# GSM-Board.net
KiCad netlist of a schematic drawn in Altium Designer
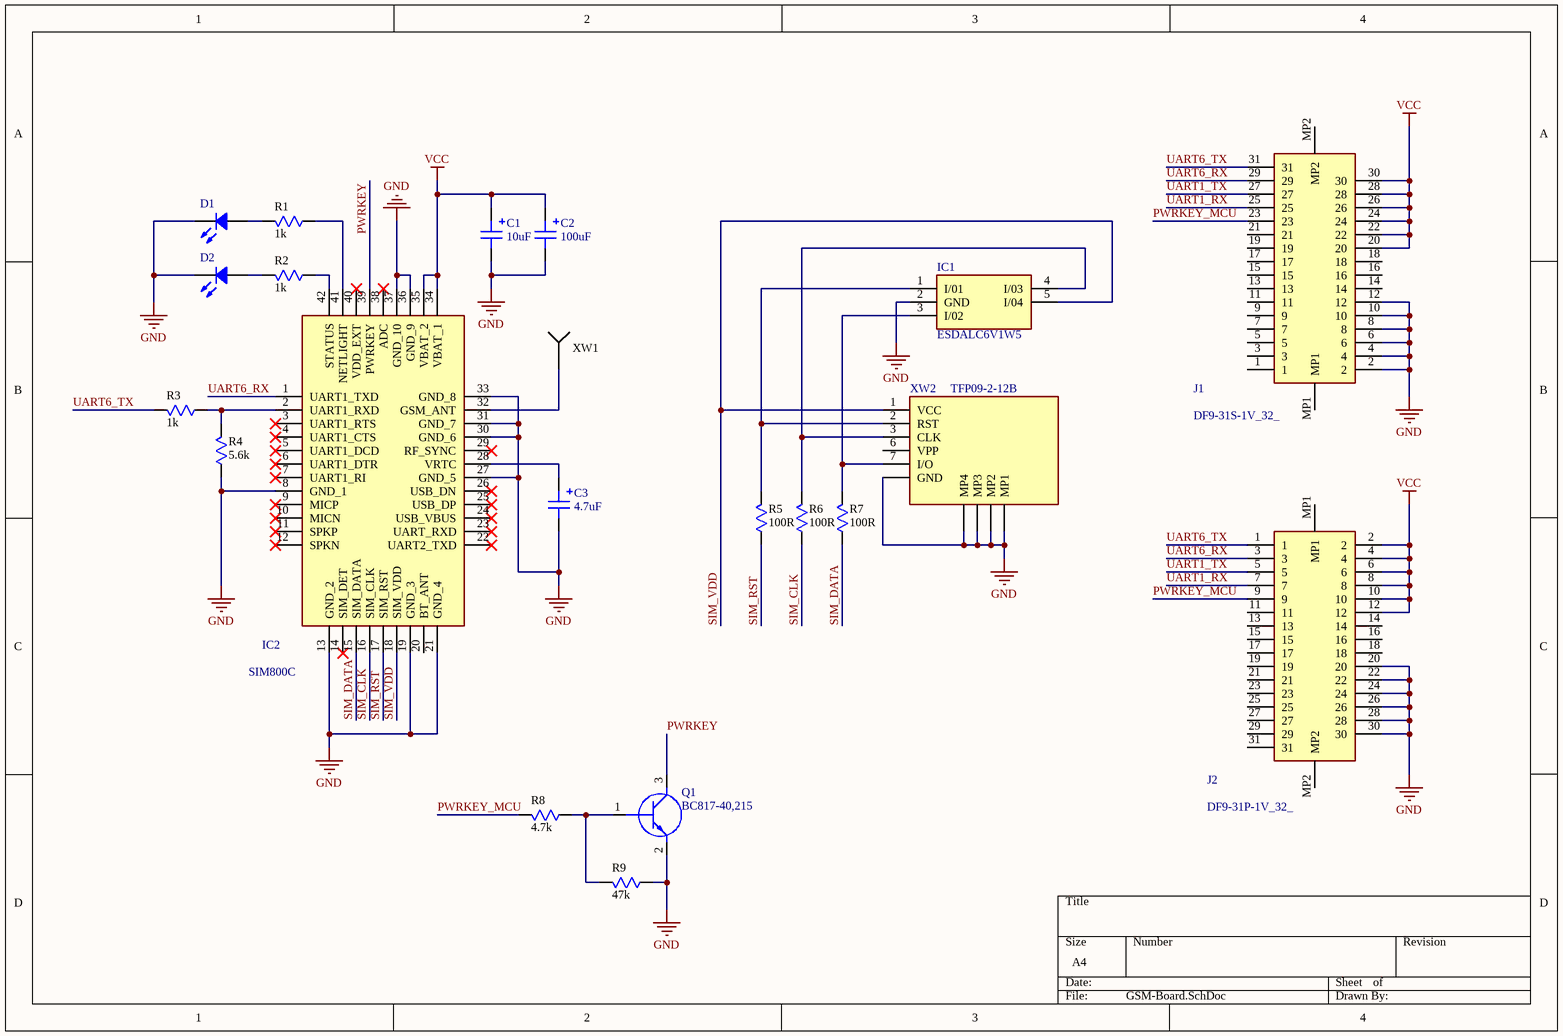
[diagram p0: GSM-Board.SchDoc]

(export (version "E")
  (design (tool "Eeschema 10.0.6"))
  (components
    (comp (ref "C1")
      (value "10uF")
      (footprint "PcbLib:CAP: TANTAL-B")
      (description "SMD Capacitor Polar")
      (libsource (lib "Schlib") (part "Capacitor_polar"))
    )
    (comp (ref "C2")
      (value "100uF")
      (footprint "PcbLib:CAP: TANTAL-D")
      (description "SMD Capacitor Polar")
      (libsource (lib "Schlib") (part "Capacitor_polar"))
    )
    (comp (ref "C3")
      (value "4.7uF")
      (footprint "PcbLib:CAP: TANTAL-A")
      (description "SMD Capacitor Polar")
      (libsource (lib "Schlib") (part "Capacitor_polar"))
    )
    (comp (ref "D1")
      (value "~")
      (footprint "PcbLib:LED0805")
      (description "Chip LED")
      (libsource (lib "Schlib") (part "LED"))
    )
    (comp (ref "D2")
      (value "~")
      (footprint "PcbLib:LED0805")
      (description "Chip LED")
      (libsource (lib "Schlib") (part "LED"))
    )
    (comp (ref "IC1")
      (value "ESDALC6V1W5")
      (footprint "PcbLib:SOT65P210X110-5N")
      (description "Integrated Circuit")
      (fields (field (name "MOUSER PART NUMBER") "511-ESDALC6V1W5"))
      (libsource (lib "*") (part "ESDALC6V1W5"))
    )
    (comp (ref "IC2")
      (value "SIM800C")
      (footprint "PcbLib:SIM800C")
      (description "Integrated Circuit")
      (fields (field (name "MANUFACTURER_PART_NUMBER") "-SIM800C"))
      (libsource (lib "Schlib") (part "-SIM800C"))
    )
    (comp (ref "J1")
      (value "DF9-31S-1V_32_")
      (footprint "PcbLib:DF931S1V32")
      (description "Connector")
      (fields
        (field (name "MANUFACTURER_PART_NUMBER") "DF9-31S-1V(32)")
        (field (name "MOUSER PART NUMBER") "798-DF9-31S-1V32")
      )
      (libsource (lib "Schlib") (part "DF9-31S-1V_32_"))
    )
    (comp (ref "J2")
      (value "DF9-31P-1V_32_")
      (footprint "PcbLib:DF931P1V32")
      (description "Connector")
      (fields
        (field (name "MANUFACTURER_PART_NUMBER") "DF9-31P-1V(32)")
        (field (name "MOUSER PART NUMBER") "798-DF9-31P-1V32")
      )
      (libsource (lib "Schlib") (part "DF9-31P-1V_32_"))
    )
    (comp (ref "Q1")
      (value "BC817-40,215")
      (footprint "PcbLib:BC81740215")
      (description "Transistor BJT NPN")
      (fields (field (name "MOUSER PART NUMBER") "771-BC817-40-T/R"))
      (libsource (lib "*") (part "BC817-40,215"))
    )
    (comp (ref "R1")
      (value "1k")
      (footprint "PcbLib:RES: 0805")
      (fields
        (field (name "MANUFACTURER") "Yageo")
        (field (name "PARTNUMBER") "RC0201JR-07100RL")
        (field (name "VALUEMANUFACTURERPARTNUMBER") "Resistor film, 1k, , 0201, 0.05W, -55...+125°C")
      )
      (libsource (lib "Schlib") (part "Resistor"))
    )
    (comp (ref "R2")
      (value "1k")
      (footprint "PcbLib:RES: 0805")
      (fields
        (field (name "MANUFACTURER") "Yageo")
        (field (name "PARTNUMBER") "RC0201JR-07100RL")
        (field (name "VALUEMANUFACTURERPARTNUMBER") "Resistor film, 1k, , 0201, 0.05W, -55...+125°C")
      )
      (libsource (lib "Schlib") (part "Resistor"))
    )
    (comp (ref "R3")
      (value "1k")
      (footprint "PcbLib:RES: 0805")
      (fields
        (field (name "MANUFACTURER") "Yageo")
        (field (name "PARTNUMBER") "RC0201JR-07100RL")
        (field (name "VALUEMANUFACTURERPARTNUMBER") "Resistor film, 1k, , 0201, 0.05W, -55...+125°C")
      )
      (libsource (lib "Schlib") (part "Resistor"))
    )
    (comp (ref "R4")
      (value "5.6k")
      (footprint "PcbLib:RES: 0805")
      (fields
        (field (name "MANUFACTURER") "Yageo")
        (field (name "PARTNUMBER") "RC0201JR-07100RL")
        (field (name "VALUEMANUFACTURERPARTNUMBER") "Resistor film, 5.6k, , 0201, 0.05W, -55...+125°C")
      )
      (libsource (lib "Schlib") (part "Resistor"))
    )
    (comp (ref "R5")
      (value "100R")
      (footprint "PcbLib:RES: 0805")
      (fields
        (field (name "MANUFACTURER") "Yageo")
        (field (name "PARTNUMBER") "RC0201JR-07100RL")
        (field (name "VALUEMANUFACTURERPARTNUMBER") "Resistor film, 100R, , 0201, 0.05W, -55...+125°C")
      )
      (libsource (lib "Schlib") (part "Resistor"))
    )
    (comp (ref "R6")
      (value "100R")
      (footprint "PcbLib:RES: 0805")
      (fields
        (field (name "MANUFACTURER") "Yageo")
        (field (name "PARTNUMBER") "RC0201JR-07100RL")
        (field (name "VALUEMANUFACTURERPARTNUMBER") "Resistor film, 100R, , 0201, 0.05W, -55...+125°C")
      )
      (libsource (lib "Schlib") (part "Resistor"))
    )
    (comp (ref "R7")
      (value "100R")
      (footprint "PcbLib:RES: 0805")
      (fields
        (field (name "MANUFACTURER") "Yageo")
        (field (name "PARTNUMBER") "RC0201JR-07100RL")
        (field (name "VALUEMANUFACTURERPARTNUMBER") "Resistor film, 100R, , 0201, 0.05W, -55...+125°C")
      )
      (libsource (lib "Schlib") (part "Resistor"))
    )
    (comp (ref "R8")
      (value "4.7k")
      (footprint "PcbLib:RES: 0805")
      (fields
        (field (name "MANUFACTURER") "Yageo")
        (field (name "PARTNUMBER") "RC0201JR-07100RL")
        (field (name "VALUEMANUFACTURERPARTNUMBER") "Resistor film, 4.7k, , 0201, 0.05W, -55...+125°C")
      )
      (libsource (lib "Schlib") (part "Resistor"))
    )
    (comp (ref "R9")
      (value "47k")
      (footprint "PcbLib:RES: 0805")
      (fields
        (field (name "MANUFACTURER") "Yageo")
        (field (name "PARTNUMBER") "RC0201JR-07100RL")
        (field (name "VALUEMANUFACTURERPARTNUMBER") "Resistor film, 47k, , 0201, 0.05W, -55...+125°C")
      )
      (libsource (lib "Schlib") (part "Resistor"))
    )
    (comp (ref "XW1")
      (value "~")
      (footprint "PcbLib:ANT_HOLE")
      (libsource (lib "Schlib") (part "Connector RF"))
    )
    (comp (ref "XW2")
      (value "TFP09-2-12B")
      (footprint "PcbLib:SIMHOLDER")
      (description "Connector")
      (libsource (lib "Schlib") (part "TFP09-2-12B"))
    )
  )
  (nets
    (net (code "1") (name "/PWRKEY") (class "Default")
      (node (ref "IC2") (pin "39") (pinfunction "PWRKEY_39") (pintype "passive"))
      (node (ref "Q1") (pin "3") (pinfunction "C_3") (pintype "passive"))
    )
    (net (code "2") (name "/PWRKEY_MCU") (class "Default")
      (node (ref "J1") (pin "23") (pinfunction "23_23") (pintype "passive"))
      (node (ref "J2") (pin "9") (pinfunction "9_9") (pintype "passive"))
      (node (ref "R8") (pin "2") (pinfunction "2_2") (pintype "passive"))
    )
    (net (code "3") (name "/SIM_CLK") (class "Default")
      (node (ref "IC2") (pin "16") (pinfunction "SIM_CLK_16") (pintype "passive"))
      (node (ref "R6") (pin "1") (pinfunction "1_1") (pintype "passive"))
    )
    (net (code "4") (name "/SIM_DATA") (class "Default")
      (node (ref "IC2") (pin "15") (pinfunction "SIM_DATA_15") (pintype "passive"))
      (node (ref "R7") (pin "1") (pinfunction "1_1") (pintype "passive"))
    )
    (net (code "5") (name "/SIM_RST") (class "Default")
      (node (ref "IC2") (pin "17") (pinfunction "SIM_RST_17") (pintype "passive"))
      (node (ref "R5") (pin "1") (pinfunction "1_1") (pintype "passive"))
    )
    (net (code "6") (name "/SIM_VDD") (class "Default")
      (node (ref "IC1") (pin "5") (pinfunction "I/04_5") (pintype "passive"))
      (node (ref "IC2") (pin "18") (pinfunction "SIM_VDD_18") (pintype "passive"))
      (node (ref "XW2") (pin "1") (pinfunction "VCC_1") (pintype "power_in"))
    )
    (net (code "7") (name "/UART1_RX") (class "Default")
      (node (ref "J1") (pin "25") (pinfunction "25_25") (pintype "passive"))
      (node (ref "J2") (pin "7") (pinfunction "7_7") (pintype "passive"))
    )
    (net (code "8") (name "/UART1_TX") (class "Default")
      (node (ref "J1") (pin "27") (pinfunction "27_27") (pintype "passive"))
      (node (ref "J2") (pin "5") (pinfunction "5_5") (pintype "passive"))
    )
    (net (code "9") (name "/UART6_RX") (class "Default")
      (node (ref "IC2") (pin "1") (pinfunction "UART1_TXD_1") (pintype "passive"))
      (node (ref "J1") (pin "29") (pinfunction "29_29") (pintype "passive"))
      (node (ref "J2") (pin "3") (pinfunction "3_3") (pintype "passive"))
    )
    (net (code "10") (name "/UART6_TX") (class "Default")
      (node (ref "J1") (pin "31") (pinfunction "31_31") (pintype "passive"))
      (node (ref "J2") (pin "1") (pinfunction "1_1") (pintype "passive"))
      (node (ref "R3") (pin "2") (pinfunction "2_2") (pintype "passive"))
    )
    (net (code "11") (name "GND") (class "Default")
      (node (ref "C1") (pin "2") (pinfunction "2_2") (pintype "passive"))
      (node (ref "C2") (pin "2") (pinfunction "2_2") (pintype "passive"))
      (node (ref "C3") (pin "2") (pinfunction "2_2") (pintype "passive"))
      (node (ref "D1") (pin "2") (pinfunction "2_2") (pintype "passive"))
      (node (ref "D2") (pin "2") (pinfunction "2_2") (pintype "passive"))
      (node (ref "IC1") (pin "2") (pinfunction "GND_2") (pintype "passive"))
      (node (ref "IC2") (pin "13") (pinfunction "GND_2_13") (pintype "passive"))
      (node (ref "IC2") (pin "19") (pinfunction "GND_3_19") (pintype "passive"))
      (node (ref "IC2") (pin "21") (pinfunction "GND_4_21") (pintype "passive"))
      (node (ref "IC2") (pin "27") (pinfunction "GND_5_27") (pintype "passive"))
      (node (ref "IC2") (pin "30") (pinfunction "GND_6_30") (pintype "passive"))
      (node (ref "IC2") (pin "31") (pinfunction "GND_7_31") (pintype "passive"))
      (node (ref "IC2") (pin "33") (pinfunction "GND_8_33") (pintype "passive"))
      (node (ref "IC2") (pin "36") (pinfunction "GND_9_36") (pintype "passive"))
      (node (ref "IC2") (pin "37") (pinfunction "GND_10_37") (pintype "passive"))
      (node (ref "IC2") (pin "8") (pinfunction "GND_1_8") (pintype "passive"))
      (node (ref "J1") (pin "10") (pinfunction "10_10") (pintype "passive"))
      (node (ref "J1") (pin "12") (pinfunction "12_12") (pintype "passive"))
      (node (ref "J1") (pin "2") (pinfunction "2_2") (pintype "passive"))
      (node (ref "J1") (pin "4") (pinfunction "4_4") (pintype "passive"))
      (node (ref "J1") (pin "6") (pinfunction "6_6") (pintype "passive"))
      (node (ref "J1") (pin "8") (pinfunction "8_8") (pintype "passive"))
      (node (ref "J2") (pin "20") (pinfunction "20_20") (pintype "passive"))
      (node (ref "J2") (pin "22") (pinfunction "22_22") (pintype "passive"))
      (node (ref "J2") (pin "24") (pinfunction "24_24") (pintype "passive"))
      (node (ref "J2") (pin "26") (pinfunction "26_26") (pintype "passive"))
      (node (ref "J2") (pin "28") (pinfunction "28_28") (pintype "passive"))
      (node (ref "J2") (pin "30") (pinfunction "30_30") (pintype "passive"))
      (node (ref "Q1") (pin "2") (pinfunction "E_2") (pintype "passive"))
      (node (ref "R4") (pin "1") (pinfunction "1_1") (pintype "passive"))
      (node (ref "R9") (pin "1") (pinfunction "1_1") (pintype "passive"))
      (node (ref "XW2") (pin "5") (pinfunction "GND_5") (pintype "power_in"))
      (node (ref "XW2") (pin "MP1") (pinfunction "MP1_MP1") (pintype "passive"))
      (node (ref "XW2") (pin "MP2") (pinfunction "MP2_MP2") (pintype "passive"))
      (node (ref "XW2") (pin "MP3") (pinfunction "MP3_MP3") (pintype "passive"))
      (node (ref "XW2") (pin "MP4") (pinfunction "MP4_MP4") (pintype "passive"))
    )
    (net (code "12") (name "Net-(D1-Pad1)") (class "Default")
      (node (ref "D1") (pin "1") (pinfunction "1_1") (pintype "passive"))
      (node (ref "R1") (pin "2") (pinfunction "2_2") (pintype "passive"))
    )
    (net (code "13") (name "Net-(D2-Pad1)") (class "Default")
      (node (ref "D2") (pin "1") (pinfunction "1_1") (pintype "passive"))
      (node (ref "R2") (pin "2") (pinfunction "2_2") (pintype "passive"))
    )
    (net (code "14") (name "Net-(IC1-I{slash}01)") (class "Default")
      (node (ref "IC1") (pin "1") (pinfunction "I/01_1") (pintype "passive"))
      (node (ref "R5") (pin "2") (pinfunction "2_2") (pintype "passive"))
      (node (ref "XW2") (pin "2") (pinfunction "RST_2") (pintype "passive"))
    )
    (net (code "15") (name "Net-(IC1-I{slash}02)") (class "Default")
      (node (ref "IC1") (pin "3") (pinfunction "I/02_3") (pintype "passive"))
      (node (ref "R7") (pin "2") (pinfunction "2_2") (pintype "passive"))
      (node (ref "XW2") (pin "7") (pinfunction "I/O_7") (pintype "passive"))
    )
    (net (code "16") (name "Net-(IC1-I{slash}03)") (class "Default")
      (node (ref "IC1") (pin "4") (pinfunction "I/03_4") (pintype "passive"))
      (node (ref "R6") (pin "2") (pinfunction "2_2") (pintype "passive"))
      (node (ref "XW2") (pin "3") (pinfunction "CLK_3") (pintype "passive"))
    )
    (net (code "17") (name "Net-(IC2-GSM_ANT)") (class "Default")
      (node (ref "IC2") (pin "32") (pinfunction "GSM_ANT_32") (pintype "passive"))
      (node (ref "XW1") (pin "1") (pinfunction "SIG_1") (pintype "passive"))
    )
    (net (code "18") (name "Net-(IC2-NETLIGHT)") (class "Default")
      (node (ref "IC2") (pin "41") (pinfunction "NETLIGHT_41") (pintype "passive"))
      (node (ref "R1") (pin "1") (pinfunction "1_1") (pintype "passive"))
    )
    (net (code "19") (name "Net-(IC2-STATUS)") (class "Default")
      (node (ref "IC2") (pin "42") (pinfunction "STATUS_42") (pintype "passive"))
      (node (ref "R2") (pin "1") (pinfunction "1_1") (pintype "passive"))
    )
    (net (code "20") (name "Net-(IC2-UART1_RXD)") (class "Default")
      (node (ref "IC2") (pin "2") (pinfunction "UART1_RXD_2") (pintype "passive"))
      (node (ref "R3") (pin "1") (pinfunction "1_1") (pintype "passive"))
      (node (ref "R4") (pin "2") (pinfunction "2_2") (pintype "passive"))
    )
    (net (code "21") (name "Net-(IC2-VRTC)") (class "Default")
      (node (ref "C3") (pin "1") (pinfunction "1_1") (pintype "passive"))
      (node (ref "IC2") (pin "28") (pinfunction "VRTC_28") (pintype "passive"))
    )
    (net (code "22") (name "Net-(Q1-B)") (class "Default")
      (node (ref "Q1") (pin "1") (pinfunction "B_1") (pintype "passive"))
      (node (ref "R8") (pin "1") (pinfunction "1_1") (pintype "passive"))
      (node (ref "R9") (pin "2") (pinfunction "2_2") (pintype "passive"))
    )
    (net (code "23") (name "VCC") (class "Default")
      (node (ref "C1") (pin "1") (pinfunction "1_1") (pintype "passive"))
      (node (ref "C2") (pin "1") (pinfunction "1_1") (pintype "passive"))
      (node (ref "IC2") (pin "34") (pinfunction "VBAT_1_34") (pintype "passive"))
      (node (ref "IC2") (pin "35") (pinfunction "VBAT_2_35") (pintype "passive"))
      (node (ref "J1") (pin "20") (pinfunction "20_20") (pintype "passive"))
      (node (ref "J1") (pin "22") (pinfunction "22_22") (pintype "passive"))
      (node (ref "J1") (pin "24") (pinfunction "24_24") (pintype "passive"))
      (node (ref "J1") (pin "26") (pinfunction "26_26") (pintype "passive"))
      (node (ref "J1") (pin "28") (pinfunction "28_28") (pintype "passive"))
      (node (ref "J1") (pin "30") (pinfunction "30_30") (pintype "passive"))
      (node (ref "J2") (pin "10") (pinfunction "10_10") (pintype "passive"))
      (node (ref "J2") (pin "12") (pinfunction "12_12") (pintype "passive"))
      (node (ref "J2") (pin "2") (pinfunction "2_2") (pintype "passive"))
      (node (ref "J2") (pin "4") (pinfunction "4_4") (pintype "passive"))
      (node (ref "J2") (pin "6") (pinfunction "6_6") (pintype "passive"))
      (node (ref "J2") (pin "8") (pinfunction "8_8") (pintype "passive"))
    )
    (net (code "24") (name "unconnected-(IC2-ADC-Pad38)") (class "Default")
      (node (ref "IC2") (pin "38") (pinfunction "ADC_38") (pintype "passive+no_connect"))
    )
    (net (code "25") (name "unconnected-(IC2-BT_ANT-Pad20)") (class "Default")
      (node (ref "IC2") (pin "20") (pinfunction "BT_ANT_20") (pintype "passive"))
    )
    (net (code "26") (name "unconnected-(IC2-MICN-Pad10)") (class "Default")
      (node (ref "IC2") (pin "10") (pinfunction "MICN_10") (pintype "passive+no_connect"))
    )
    (net (code "27") (name "unconnected-(IC2-MICP-Pad9)") (class "Default")
      (node (ref "IC2") (pin "9") (pinfunction "MICP_9") (pintype "passive+no_connect"))
    )
    (net (code "28") (name "unconnected-(IC2-RF_SYNC-Pad29)") (class "Default")
      (node (ref "IC2") (pin "29") (pinfunction "RF_SYNC_29") (pintype "passive+no_connect"))
    )
    (net (code "29") (name "unconnected-(IC2-SIM_DET-Pad14)") (class "Default")
      (node (ref "IC2") (pin "14") (pinfunction "SIM_DET_14") (pintype "passive+no_connect"))
    )
    (net (code "30") (name "unconnected-(IC2-SPKN-Pad12)") (class "Default")
      (node (ref "IC2") (pin "12") (pinfunction "SPKN_12") (pintype "passive+no_connect"))
    )
    (net (code "31") (name "unconnected-(IC2-SPKP-Pad11)") (class "Default")
      (node (ref "IC2") (pin "11") (pinfunction "SPKP_11") (pintype "passive+no_connect"))
    )
    (net (code "32") (name "unconnected-(IC2-UART1_CTS-Pad4)") (class "Default")
      (node (ref "IC2") (pin "4") (pinfunction "UART1_CTS_4") (pintype "passive+no_connect"))
    )
    (net (code "33") (name "unconnected-(IC2-UART1_DCD-Pad5)") (class "Default")
      (node (ref "IC2") (pin "5") (pinfunction "UART1_DCD_5") (pintype "passive+no_connect"))
    )
    (net (code "34") (name "unconnected-(IC2-UART1_DTR-Pad6)") (class "Default")
      (node (ref "IC2") (pin "6") (pinfunction "UART1_DTR_6") (pintype "passive+no_connect"))
    )
    (net (code "35") (name "unconnected-(IC2-UART1_RI-Pad7)") (class "Default")
      (node (ref "IC2") (pin "7") (pinfunction "UART1_RI_7") (pintype "passive+no_connect"))
    )
    (net (code "36") (name "unconnected-(IC2-UART1_RTS-Pad3)") (class "Default")
      (node (ref "IC2") (pin "3") (pinfunction "UART1_RTS_3") (pintype "passive+no_connect"))
    )
    (net (code "37") (name "unconnected-(IC2-UART2_TXD-Pad22)") (class "Default")
      (node (ref "IC2") (pin "22") (pinfunction "UART2_TXD_22") (pintype "passive+no_connect"))
    )
    (net (code "38") (name "unconnected-(IC2-UART_RXD-Pad23)") (class "Default")
      (node (ref "IC2") (pin "23") (pinfunction "UART_RXD_23") (pintype "passive+no_connect"))
    )
    (net (code "39") (name "unconnected-(IC2-USB_DN-Pad26)") (class "Default")
      (node (ref "IC2") (pin "26") (pinfunction "USB_DN_26") (pintype "passive+no_connect"))
    )
    (net (code "40") (name "unconnected-(IC2-USB_DP-Pad25)") (class "Default")
      (node (ref "IC2") (pin "25") (pinfunction "USB_DP_25") (pintype "passive+no_connect"))
    )
    (net (code "41") (name "unconnected-(IC2-USB_VBUS-Pad24)") (class "Default")
      (node (ref "IC2") (pin "24") (pinfunction "USB_VBUS_24") (pintype "passive+no_connect"))
    )
    (net (code "42") (name "unconnected-(IC2-VDD_EXT-Pad40)") (class "Default")
      (node (ref "IC2") (pin "40") (pinfunction "VDD_EXT_40") (pintype "passive+no_connect"))
    )
    (net (code "43") (name "unconnected-(J1-Pad1)") (class "Default")
      (node (ref "J1") (pin "1") (pinfunction "1_1") (pintype "passive"))
    )
    (net (code "44") (name "unconnected-(J1-Pad3)") (class "Default")
      (node (ref "J1") (pin "3") (pinfunction "3_3") (pintype "passive"))
    )
    (net (code "45") (name "unconnected-(J1-Pad5)") (class "Default")
      (node (ref "J1") (pin "5") (pinfunction "5_5") (pintype "passive"))
    )
    (net (code "46") (name "unconnected-(J1-Pad7)") (class "Default")
      (node (ref "J1") (pin "7") (pinfunction "7_7") (pintype "passive"))
    )
    (net (code "47") (name "unconnected-(J1-Pad9)") (class "Default")
      (node (ref "J1") (pin "9") (pinfunction "9_9") (pintype "passive"))
    )
    (net (code "48") (name "unconnected-(J1-Pad11)") (class "Default")
      (node (ref "J1") (pin "11") (pinfunction "11_11") (pintype "passive"))
    )
    (net (code "49") (name "unconnected-(J1-Pad13)") (class "Default")
      (node (ref "J1") (pin "13") (pinfunction "13_13") (pintype "passive"))
    )
    (net (code "50") (name "unconnected-(J1-Pad14)") (class "Default")
      (node (ref "J1") (pin "14") (pinfunction "14_14") (pintype "passive"))
    )
    (net (code "51") (name "unconnected-(J1-Pad15)") (class "Default")
      (node (ref "J1") (pin "15") (pinfunction "15_15") (pintype "passive"))
    )
    (net (code "52") (name "unconnected-(J1-Pad16)") (class "Default")
      (node (ref "J1") (pin "16") (pinfunction "16_16") (pintype "passive"))
    )
    (net (code "53") (name "unconnected-(J1-Pad17)") (class "Default")
      (node (ref "J1") (pin "17") (pinfunction "17_17") (pintype "passive"))
    )
    (net (code "54") (name "unconnected-(J1-Pad18)") (class "Default")
      (node (ref "J1") (pin "18") (pinfunction "18_18") (pintype "passive"))
    )
    (net (code "55") (name "unconnected-(J1-Pad19)") (class "Default")
      (node (ref "J1") (pin "19") (pinfunction "19_19") (pintype "passive"))
    )
    (net (code "56") (name "unconnected-(J1-Pad21)") (class "Default")
      (node (ref "J1") (pin "21") (pinfunction "21_21") (pintype "passive"))
    )
    (net (code "57") (name "unconnected-(J1-PadMP1)") (class "Default")
      (node (ref "J1") (pin "MP1") (pinfunction "MP1_MP1") (pintype "passive"))
    )
    (net (code "58") (name "unconnected-(J1-PadMP2)") (class "Default")
      (node (ref "J1") (pin "MP2") (pinfunction "MP2_MP2") (pintype "passive"))
    )
    (net (code "59") (name "unconnected-(J2-Pad11)") (class "Default")
      (node (ref "J2") (pin "11") (pinfunction "11_11") (pintype "passive"))
    )
    (net (code "60") (name "unconnected-(J2-Pad13)") (class "Default")
      (node (ref "J2") (pin "13") (pinfunction "13_13") (pintype "passive"))
    )
    (net (code "61") (name "unconnected-(J2-Pad14)") (class "Default")
      (node (ref "J2") (pin "14") (pinfunction "14_14") (pintype "passive"))
    )
    (net (code "62") (name "unconnected-(J2-Pad15)") (class "Default")
      (node (ref "J2") (pin "15") (pinfunction "15_15") (pintype "passive"))
    )
    (net (code "63") (name "unconnected-(J2-Pad16)") (class "Default")
      (node (ref "J2") (pin "16") (pinfunction "16_16") (pintype "passive"))
    )
    (net (code "64") (name "unconnected-(J2-Pad17)") (class "Default")
      (node (ref "J2") (pin "17") (pinfunction "17_17") (pintype "passive"))
    )
    (net (code "65") (name "unconnected-(J2-Pad18)") (class "Default")
      (node (ref "J2") (pin "18") (pinfunction "18_18") (pintype "passive"))
    )
    (net (code "66") (name "unconnected-(J2-Pad19)") (class "Default")
      (node (ref "J2") (pin "19") (pinfunction "19_19") (pintype "passive"))
    )
    (net (code "67") (name "unconnected-(J2-Pad21)") (class "Default")
      (node (ref "J2") (pin "21") (pinfunction "21_21") (pintype "passive"))
    )
    (net (code "68") (name "unconnected-(J2-Pad23)") (class "Default")
      (node (ref "J2") (pin "23") (pinfunction "23_23") (pintype "passive"))
    )
    (net (code "69") (name "unconnected-(J2-Pad25)") (class "Default")
      (node (ref "J2") (pin "25") (pinfunction "25_25") (pintype "passive"))
    )
    (net (code "70") (name "unconnected-(J2-Pad27)") (class "Default")
      (node (ref "J2") (pin "27") (pinfunction "27_27") (pintype "passive"))
    )
    (net (code "71") (name "unconnected-(J2-Pad29)") (class "Default")
      (node (ref "J2") (pin "29") (pinfunction "29_29") (pintype "passive"))
    )
    (net (code "72") (name "unconnected-(J2-Pad31)") (class "Default")
      (node (ref "J2") (pin "31") (pinfunction "31_31") (pintype "passive"))
    )
    (net (code "73") (name "unconnected-(J2-PadMP1)") (class "Default")
      (node (ref "J2") (pin "MP1") (pinfunction "MP1_MP1") (pintype "passive"))
    )
    (net (code "74") (name "unconnected-(J2-PadMP2)") (class "Default")
      (node (ref "J2") (pin "MP2") (pinfunction "MP2_MP2") (pintype "passive"))
    )
    (net (code "75") (name "unconnected-(XW2-VPP-Pad6)") (class "Default")
      (node (ref "XW2") (pin "6") (pinfunction "VPP_6") (pintype "passive"))
    )
  )
)
